# HV_Sense.net
KiCad netlist of a schematic drawn in Altium Designer
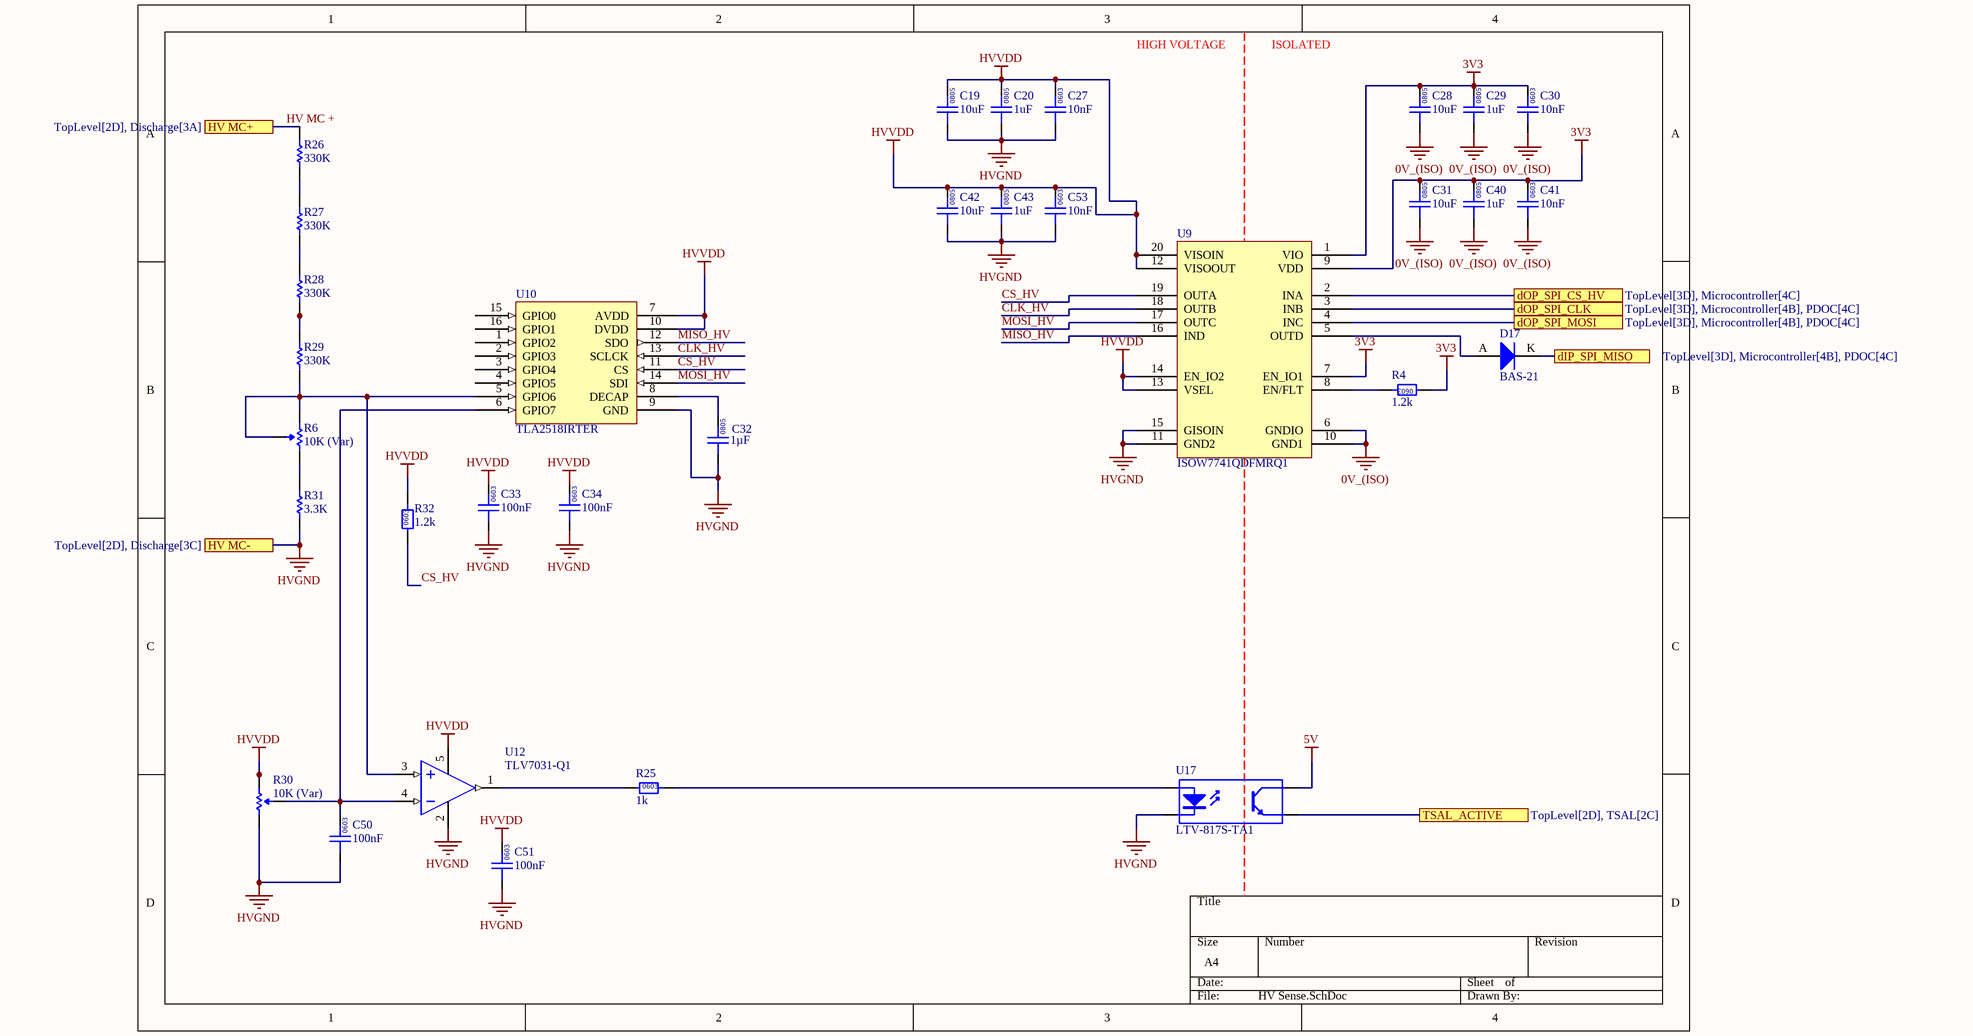
[diagram p0: HV Sense.SchDoc]

(export (version "E")
  (design (tool "Eeschema 10.0.6"))
  (components
    (comp (ref "C19")
      (value "10uF")
      (footprint "GCM21BR71H105KA03L-Footprint-1")
      (fields (field (name "PART NUMBER") "GRM21BR6YA106KE43L") (field (name "TOLERANCE") "10%"))
      (libsource (lib "Team Swinburne") (part "Component_1"))
    )
    (comp (ref "C20")
      (value "1uF")
      (footprint "GCM21BR71H105KA03L-Footprint-1")
      (fields (field (name "TOLERANCE") "10%") (field (name "PART NUMBER") "GCM21BR71H105KA03L"))
      (libsource (lib "Team Swinburne") (part "Component_1"))
    )
    (comp (ref "C27")
      (value "10nF")
      (footprint "0603 Capacitor")
      (fields (field (name "PART NUMBER") "GCM1885C1H103JA16D") (field (name "TOLERANCE") "5%"))
      (libsource (lib "Team Swinburne") (part "10nF"))
    )
    (comp (ref "C28")
      (value "10uF")
      (footprint "GCM21BR71H105KA03L-Footprint-1")
      (fields (field (name "PART NUMBER") "GRM21BR6YA106KE43L") (field (name "TOLERANCE") "10%"))
      (libsource (lib "Team Swinburne") (part "Component_1"))
    )
    (comp (ref "C29")
      (value "1uF")
      (footprint "GCM21BR71H105KA03L-Footprint-1")
      (fields (field (name "TOLERANCE") "10%") (field (name "PART NUMBER") "GCM21BR71H105KA03L"))
      (libsource (lib "Team Swinburne") (part "Component_1"))
    )
    (comp (ref "C30")
      (value "10nF")
      (footprint "0603 Capacitor")
      (fields (field (name "PART NUMBER") "GCM1885C1H103JA16D") (field (name "TOLERANCE") "5%"))
      (libsource (lib "Team Swinburne") (part "10nF"))
    )
    (comp (ref "C31")
      (value "10uF")
      (footprint "GCM21BR71H105KA03L-Footprint-1")
      (fields (field (name "PART NUMBER") "GRM21BR6YA106KE43L") (field (name "TOLERANCE") "10%"))
      (libsource (lib "Team Swinburne") (part "Component_1"))
    )
    (comp (ref "C32")
      (value "1µF")
      (footprint "0805")
      (fields
        (field (name "PART NUMBER") "GCM21BR71H105KA03L")
        (field (name "MANUFACTURER") "muRata")
        (field (name "TOLERANCE") "±10%")
      )
      (libsource (lib "ts_standard_library") (part "Capacitor 0805"))
    )
    (comp (ref "C33")
      (value "100nF")
      (footprint "0603")
      (fields
        (field (name "PART NUMBER") "GCM188L81H104KA57D")
        (field (name "MANUFACTURER") "muRata")
        (field (name "TOLERANCE") "±10%")
      )
      (libsource (lib "ts_standard_library") (part "Capacitor 0603"))
    )
    (comp (ref "C34")
      (value "100nF")
      (footprint "0603")
      (fields
        (field (name "PART NUMBER") "GCM188L81H104KA57D")
        (field (name "MANUFACTURER") "muRata")
        (field (name "TOLERANCE") "±10%")
      )
      (libsource (lib "ts_standard_library") (part "Capacitor 0603"))
    )
    (comp (ref "C40")
      (value "1uF")
      (footprint "GCM21BR71H105KA03L-Footprint-1")
      (fields (field (name "TOLERANCE") "10%") (field (name "PART NUMBER") "GCM21BR71H105KA03L"))
      (libsource (lib "Team Swinburne") (part "Component_1"))
    )
    (comp (ref "C41")
      (value "10nF")
      (footprint "0603 Capacitor")
      (fields (field (name "PART NUMBER") "GCM1885C1H103JA16D") (field (name "TOLERANCE") "5%"))
      (libsource (lib "Team Swinburne") (part "10nF"))
    )
    (comp (ref "C42")
      (value "10uF")
      (footprint "GCM21BR71H105KA03L-Footprint-1")
      (fields (field (name "PART NUMBER") "GRM21BR6YA106KE43L") (field (name "TOLERANCE") "10%"))
      (libsource (lib "Team Swinburne") (part "Component_1"))
    )
    (comp (ref "C43")
      (value "1uF")
      (footprint "GCM21BR71H105KA03L-Footprint-1")
      (fields (field (name "TOLERANCE") "10%") (field (name "PART NUMBER") "GCM21BR71H105KA03L"))
      (libsource (lib "Team Swinburne") (part "Component_1"))
    )
    (comp (ref "C50")
      (value "100nF")
      (footprint "0603")
      (fields
        (field (name "PART NUMBER") "GCM188L81H104KA57D")
        (field (name "MANUFACTURER") "muRata")
        (field (name "TOLERANCE") "±10%")
      )
      (libsource (lib "ts_standard_library") (part "Capacitor 0603"))
    )
    (comp (ref "C51")
      (value "100nF")
      (footprint "0603")
      (fields
        (field (name "PART NUMBER") "GCM188L81H104KA57D")
        (field (name "MANUFACTURER") "muRata")
        (field (name "TOLERANCE") "±10%")
      )
      (libsource (lib "ts_standard_library") (part "Capacitor 0603"))
    )
    (comp (ref "C53")
      (value "10nF")
      (footprint "0603 Capacitor")
      (fields (field (name "PART NUMBER") "GCM1885C1H103JA16D") (field (name "TOLERANCE") "5%"))
      (libsource (lib "Team Swinburne") (part "10nF"))
    )
    (comp (ref "D17")
      (value "BAS-21")
      (footprint "NEXPERIA_SOT23")
      (fields (field (name "MANUFACTURER") "Nexperia USA Inc."))
      (libsource (lib "ts_standard_library") (part "Diode"))
    )
    (comp (ref "R4")
      (value "1.2k")
      (footprint "0603")
      (fields
        (field (name "PART NUMBER") "RC0603JR-071K2L")
        (field (name "MANUFACTURER") "YAGEO")
        (field (name "TOLERANCE") "0.01")
      )
      (libsource (lib "ts_standard_library") (part "Resistor 0603"))
    )
    (comp (ref "R6")
      (value "10K (Var)")
      (footprint "B 3296")
      (fields
        (field (name "PART NUMBER") "3296W-1-103LF")
        (field (name "MANUFACTURER") "Bournes Inc")
        (field (name "TOLERANCE") "0.1")
      )
      (libsource (lib "ts_standard_library") (part "Resistor (Potentiometer)"))
    )
    (comp (ref "R25")
      (value "1k")
      (footprint "0603")
      (fields
        (field (name "PART NUMBER") "RC0603FR-071KL")
        (field (name "MANUFACTURER") "YAGEO")
        (field (name "TOLERANCE") "0.01")
      )
      (libsource (lib "ts_standard_library") (part "Resistor 0603"))
    )
    (comp (ref "R26")
      (value "330K")
      (footprint "VB 0207")
      (fields
        (field (name "PART NUMBER") "MMB02070C3303FB200")
        (field (name "MANUFACTURER") "Vishay Beyschlag")
        (field (name "TOLERANCE") "0.01")
      )
      (libsource (lib "ts_standard_library") (part "Resistor"))
    )
    (comp (ref "R27")
      (value "330K")
      (footprint "VB 0207")
      (fields
        (field (name "PART NUMBER") "MMB02070C3303FB200")
        (field (name "MANUFACTURER") "Vishay Beyschlag")
        (field (name "TOLERANCE") "0.01")
      )
      (libsource (lib "ts_standard_library") (part "Resistor"))
    )
    (comp (ref "R28")
      (value "330K")
      (footprint "VB 0207")
      (fields
        (field (name "PART NUMBER") "MMB02070C3303FB200")
        (field (name "MANUFACTURER") "Vishay Beyschlag")
        (field (name "TOLERANCE") "0.01")
      )
      (libsource (lib "ts_standard_library") (part "Resistor"))
    )
    (comp (ref "R29")
      (value "330K")
      (footprint "VB 0207")
      (fields
        (field (name "PART NUMBER") "MMB02070C3303FB200")
        (field (name "MANUFACTURER") "Vishay Beyschlag")
        (field (name "TOLERANCE") "0.01")
      )
      (libsource (lib "ts_standard_library") (part "Resistor"))
    )
    (comp (ref "R30")
      (value "10K (Var)")
      (footprint "B 3296")
      (fields
        (field (name "PART NUMBER") "3296W-1-103LF")
        (field (name "MANUFACTURER") "Bournes Inc")
        (field (name "TOLERANCE") "0.1")
      )
      (libsource (lib "ts_standard_library") (part "Resistor (Potentiometer)"))
    )
    (comp (ref "R31")
      (value "3.3K")
      (footprint "VB 0207")
      (fields
        (field (name "PART NUMBER") "MMB02070C3301FB200")
        (field (name "MANUFACTURER") "Vishay Beyschlag")
        (field (name "TOLERANCE") "0.01")
      )
      (libsource (lib "ts_20-standard-library") (part "Resistor"))
    )
    (comp (ref "R32")
      (value "1.2k")
      (footprint "0603")
      (fields
        (field (name "PART NUMBER") "RC0603JR-071K2L")
        (field (name "MANUFACTURER") "YAGEO")
        (field (name "TOLERANCE") "0.01")
      )
      (libsource (lib "ts_standard_library") (part "Resistor 0603"))
    )
    (comp (ref "U9")
      (value "ISOW7741QDFMRQ1")
      (footprint "TI-SOIC-20")
      (libsource (lib "Team Swinburne") (part "ISOW7741QDFMRQ1"))
    )
    (comp (ref "U10")
      (value "TLA2518IRTER")
      (footprint "QFN50P300X300X80_HS-17N")
      (description "8-Channel Single ADC SAR 1Msps 12-bit Serial 16-Pin WQFN EP T/R")
      (libsource (lib "Team Swinburne") (part "TLA518IRTER"))
    )
    (comp (ref "U12")
      (value "TLV7031-Q1")
      (footprint "TI SOT-23-5")
      (fields
        (field (name "MANUFACTURER") "Texas Instruments")
        (field (name "DIGIKEY PART NUMBER") "296-TLV7031QDBVRQ1CT-ND")
      )
      (libsource (lib "ts_standard_library") (part "TLV7031-Q1"))
    )
    (comp (ref "U17")
      (value "LTV-817S-TA1")
      (footprint "ON 4-SMD")
      (description "35V 50ma Optocoupler (VF=1.2V)")
      (fields
        (field (name "MANUFACTURER") "Lite-On Inc")
        (field (name "DIGIKEY PART NUMBER") "160-1893-2-ND")
      )
      (libsource (lib "ts_20-standard-library") (part "LTV-817S-TA1"))
    )
  )
  (nets
    (net (code "1") (name "/CLK_HV") (class "Default")
      (node (ref "U10") (pin "13") (pinfunction "SCLCK_13") (pintype "input"))
      (node (ref "U9") (pin "18") (pinfunction "OUTB_18") (pintype "passive"))
    )
    (net (code "2") (name "/CS_HV") (class "Default")
      (node (ref "R32") (pin "1") (pinfunction "1_1") (pintype "passive"))
      (node (ref "U10") (pin "11") (pinfunction "CS_11") (pintype "input"))
      (node (ref "U9") (pin "19") (pinfunction "OUTA_19") (pintype "passive"))
    )
    (net (code "3") (name "/HV MC +") (class "Default")
      (node (ref "R26") (pin "2") (pinfunction "2_2") (pintype "passive"))
    )
    (net (code "4") (name "/MISO_HV") (class "Default")
      (node (ref "U10") (pin "12") (pinfunction "SDO_12") (pintype "output"))
      (node (ref "U9") (pin "16") (pinfunction "IND_16") (pintype "passive"))
    )
    (net (code "5") (name "/MOSI_HV") (class "Default")
      (node (ref "U10") (pin "14") (pinfunction "SDI_14") (pintype "input"))
      (node (ref "U9") (pin "17") (pinfunction "OUTC_17") (pintype "passive"))
    )
    (net (code "6") (name "/TSAL_ACTIVE") (class "Default")
      (node (ref "U17") (pin "3") (pinfunction "E_3") (pintype "passive"))
    )
    (net (code "7") (name "/dIP_SPI_MISO") (class "Default")
      (node (ref "D17") (pin "K") (pinfunction "K_K") (pintype "passive"))
    )
    (net (code "8") (name "/dOP_SPI_CLK") (class "Default")
      (node (ref "U9") (pin "3") (pinfunction "INB_3") (pintype "passive"))
    )
    (net (code "9") (name "/dOP_SPI_CS_HV") (class "Default")
      (node (ref "U9") (pin "2") (pinfunction "INA_2") (pintype "passive"))
    )
    (net (code "10") (name "/dOP_SPI_MOSI") (class "Default")
      (node (ref "U9") (pin "4") (pinfunction "INC_4") (pintype "passive"))
    )
    (net (code "11") (name "0V_(ISO)") (class "Default")
      (node (ref "C28") (pin "1") (pinfunction "1_1") (pintype "passive"))
      (node (ref "C29") (pin "1") (pinfunction "1_1") (pintype "passive"))
      (node (ref "C30") (pin "1") (pinfunction "1_1") (pintype "passive"))
      (node (ref "C31") (pin "1") (pinfunction "1_1") (pintype "passive"))
      (node (ref "C40") (pin "1") (pinfunction "1_1") (pintype "passive"))
      (node (ref "C41") (pin "1") (pinfunction "1_1") (pintype "passive"))
      (node (ref "U9") (pin "10") (pinfunction "GND1_10") (pintype "passive"))
      (node (ref "U9") (pin "6") (pinfunction "GNDIO_6") (pintype "passive"))
    )
    (net (code "12") (name "3V3") (class "Default")
      (node (ref "C28") (pin "2") (pinfunction "2_2") (pintype "passive"))
      (node (ref "C29") (pin "2") (pinfunction "2_2") (pintype "passive"))
      (node (ref "C30") (pin "2") (pinfunction "2_2") (pintype "passive"))
      (node (ref "C31") (pin "2") (pinfunction "2_2") (pintype "passive"))
      (node (ref "C40") (pin "2") (pinfunction "2_2") (pintype "passive"))
      (node (ref "C41") (pin "2") (pinfunction "2_2") (pintype "passive"))
      (node (ref "R4") (pin "1") (pinfunction "1_1") (pintype "passive"))
      (node (ref "U9") (pin "1") (pinfunction "VIO_1") (pintype "passive"))
      (node (ref "U9") (pin "7") (pinfunction "EN_IO1_7") (pintype "passive"))
      (node (ref "U9") (pin "9") (pinfunction "VDD_9") (pintype "passive"))
    )
    (net (code "13") (name "5V") (class "Default")
      (node (ref "U17") (pin "4") (pinfunction "C_4") (pintype "passive"))
    )
    (net (code "14") (name "HVGND") (class "Default")
      (node (ref "C19") (pin "1") (pinfunction "1_1") (pintype "passive"))
      (node (ref "C20") (pin "1") (pinfunction "1_1") (pintype "passive"))
      (node (ref "C27") (pin "1") (pinfunction "1_1") (pintype "passive"))
      (node (ref "C32") (pin "1") (pinfunction "1_1") (pintype "passive"))
      (node (ref "C33") (pin "1") (pinfunction "1_1") (pintype "passive"))
      (node (ref "C34") (pin "1") (pinfunction "1_1") (pintype "passive"))
      (node (ref "C42") (pin "1") (pinfunction "1_1") (pintype "passive"))
      (node (ref "C43") (pin "1") (pinfunction "1_1") (pintype "passive"))
      (node (ref "C50") (pin "1") (pinfunction "1_1") (pintype "passive"))
      (node (ref "C51") (pin "1") (pinfunction "1_1") (pintype "passive"))
      (node (ref "C53") (pin "1") (pinfunction "1_1") (pintype "passive"))
      (node (ref "R30") (pin "3") (pinfunction "CW_3") (pintype "passive"))
      (node (ref "R31") (pin "1") (pinfunction "1_1") (pintype "passive"))
      (node (ref "U10") (pin "9") (pinfunction "GND_9") (pintype "power_in"))
      (node (ref "U12") (pin "2") (pinfunction "V-_2") (pintype "power_in"))
      (node (ref "U17") (pin "2") (pinfunction "K_2") (pintype "passive"))
      (node (ref "U9") (pin "11") (pinfunction "GND2_11") (pintype "passive"))
      (node (ref "U9") (pin "15") (pinfunction "GISOIN_15") (pintype "passive"))
    )
    (net (code "15") (name "HVVDD") (class "Default")
      (node (ref "C19") (pin "2") (pinfunction "2_2") (pintype "passive"))
      (node (ref "C20") (pin "2") (pinfunction "2_2") (pintype "passive"))
      (node (ref "C27") (pin "2") (pinfunction "2_2") (pintype "passive"))
      (node (ref "C33") (pin "2") (pinfunction "2_2") (pintype "passive"))
      (node (ref "C34") (pin "2") (pinfunction "2_2") (pintype "passive"))
      (node (ref "C42") (pin "2") (pinfunction "2_2") (pintype "passive"))
      (node (ref "C43") (pin "2") (pinfunction "2_2") (pintype "passive"))
      (node (ref "C51") (pin "2") (pinfunction "2_2") (pintype "passive"))
      (node (ref "C53") (pin "2") (pinfunction "2_2") (pintype "passive"))
      (node (ref "R30") (pin "1") (pinfunction "CCW_1") (pintype "passive"))
      (node (ref "R32") (pin "2") (pinfunction "2_2") (pintype "passive"))
      (node (ref "U10") (pin "10") (pinfunction "DVDD_10") (pintype "power_in"))
      (node (ref "U10") (pin "7") (pinfunction "AVDD_7") (pintype "power_in"))
      (node (ref "U12") (pin "5") (pinfunction "Vcc_5") (pintype "power_in"))
      (node (ref "U9") (pin "12") (pinfunction "VISOOUT_12") (pintype "passive"))
      (node (ref "U9") (pin "13") (pinfunction "VSEL_13") (pintype "passive"))
      (node (ref "U9") (pin "14") (pinfunction "EN_IO2_14") (pintype "passive"))
      (node (ref "U9") (pin "20") (pinfunction "VISOIN_20") (pintype "passive"))
    )
    (net (code "16") (name "Net-(R6-CCW)") (class "Default")
      (node (ref "R31") (pin "2") (pinfunction "2_2") (pintype "passive"))
      (node (ref "R6") (pin "1") (pinfunction "CCW_1") (pintype "passive"))
    )
    (net (code "17") (name "Net-(R6-CW)") (class "Default")
      (node (ref "R29") (pin "1") (pinfunction "1_1") (pintype "passive"))
      (node (ref "R6") (pin "2") (pinfunction "Wiper_2") (pintype "passive"))
      (node (ref "R6") (pin "3") (pinfunction "CW_3") (pintype "passive"))
      (node (ref "U10") (pin "5") (pinfunction "GPIO6_5") (pintype "input"))
      (node (ref "U12") (pin "3") (pinfunction "IN+_3") (pintype "input"))
    )
    (net (code "18") (name "Net-(R26-Pad1)") (class "Default")
      (node (ref "R26") (pin "1") (pinfunction "1_1") (pintype "passive"))
      (node (ref "R27") (pin "2") (pinfunction "2_2") (pintype "passive"))
    )
    (net (code "19") (name "Net-(R27-Pad1)") (class "Default")
      (node (ref "R27") (pin "1") (pinfunction "1_1") (pintype "passive"))
      (node (ref "R28") (pin "2") (pinfunction "2_2") (pintype "passive"))
    )
    (net (code "20") (name "Net-(R28-Pad1)") (class "Default")
      (node (ref "R28") (pin "1") (pinfunction "1_1") (pintype "passive"))
      (node (ref "R29") (pin "2") (pinfunction "2_2") (pintype "passive"))
    )
    (net (code "21") (name "Net-(R30-Wiper)") (class "Default")
      (node (ref "C50") (pin "2") (pinfunction "2_2") (pintype "passive"))
      (node (ref "R30") (pin "2") (pinfunction "Wiper_2") (pintype "passive"))
      (node (ref "U10") (pin "6") (pinfunction "GPIO7_6") (pintype "input"))
      (node (ref "U12") (pin "4") (pinfunction "IN-_4") (pintype "input"))
    )
    (net (code "22") (name "Net-(U9-EN{slash}FLT)") (class "Default")
      (node (ref "R4") (pin "2") (pinfunction "2_2") (pintype "passive"))
      (node (ref "U9") (pin "8") (pinfunction "EN/FLT_8") (pintype "passive"))
    )
    (net (code "23") (name "Net-(U9-OUTD)") (class "Default")
      (node (ref "D17") (pin "A") (pinfunction "A_A") (pintype "passive"))
      (node (ref "U9") (pin "5") (pinfunction "OUTD_5") (pintype "passive"))
    )
    (net (code "24") (name "Net-(U10-DECAP)") (class "Default")
      (node (ref "C32") (pin "2") (pinfunction "2_2") (pintype "passive"))
      (node (ref "U10") (pin "8") (pinfunction "DECAP_8") (pintype "power_in"))
    )
    (net (code "25") (name "Net-(U12-OUT)") (class "Default")
      (node (ref "R25") (pin "1") (pinfunction "1_1") (pintype "passive"))
      (node (ref "U12") (pin "1") (pinfunction "OUT_1") (pintype "output"))
    )
    (net (code "26") (name "Net-(U17-A)") (class "Default")
      (node (ref "R25") (pin "2") (pinfunction "2_2") (pintype "passive"))
      (node (ref "U17") (pin "1") (pinfunction "A_1") (pintype "passive"))
    )
    (net (code "27") (name "unconnected-(U10-GPIO0-Pad15)") (class "Default")
      (node (ref "U10") (pin "15") (pinfunction "GPIO0_15") (pintype "input"))
    )
    (net (code "28") (name "unconnected-(U10-GPIO1-Pad16)") (class "Default")
      (node (ref "U10") (pin "16") (pinfunction "GPIO1_16") (pintype "input"))
    )
    (net (code "29") (name "unconnected-(U10-GPIO2-Pad1)") (class "Default")
      (node (ref "U10") (pin "1") (pinfunction "GPIO2_1") (pintype "input"))
    )
    (net (code "30") (name "unconnected-(U10-GPIO3-Pad2)") (class "Default")
      (node (ref "U10") (pin "2") (pinfunction "GPIO3_2") (pintype "input"))
    )
    (net (code "31") (name "unconnected-(U10-GPIO4-Pad3)") (class "Default")
      (node (ref "U10") (pin "3") (pinfunction "GPIO4_3") (pintype "input"))
    )
    (net (code "32") (name "unconnected-(U10-GPIO5-Pad4)") (class "Default")
      (node (ref "U10") (pin "4") (pinfunction "GPIO5_4") (pintype "input"))
    )
  )
)
